# PSU_MAX1831_1V0_ALT.net
KiCad netlist of a schematic drawn in Altium Designer
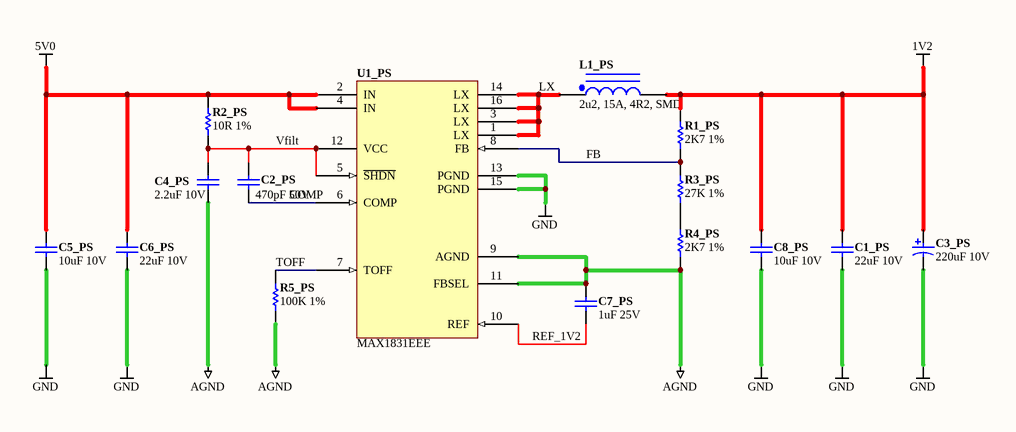
[diagram p0: PSU_MAX1831_1V0_ALT.SchDoc]

(export (version "E")
  (design (tool "Eeschema 10.0.6"))
  (components
    (comp (ref "C1_PS")
      (value "22uF 10V")
      (footprint "CAPC3225-STAR")
      (description "Capacitor, Ceramic, 22uF -20%/+80% 10V 1210 (3225) Y5V")
      (fields (field (name "TOLERANCE") "-20 / +80 %"))
      (libsource (lib "AltiumDesignLibrary") (part "CAP-NP"))
    )
    (comp (ref "C2_PS")
      (value "470pF 50V")
      (footprint "CAPC1005-STAR")
      (description "Capacitor, Ceramic, 470pF 5% 50V 0402 (1005) COG")
      (fields (field (name "TOLERANCE") "5 %"))
      (libsource (lib "AltiumDesignLibrary") (part "CAP-NP"))
    )
    (comp (ref "C3_PS")
      (value "220uF 10V")
      (footprint "CAPC7343-STAR")
      (description "Capacitor, Tantalum, 220uF 10% 10V MCCT-D (7343-31)")
      (fields (field (name "TOLERANCE") "10 %"))
      (libsource (lib "AltiumDesignLibrary") (part "CAP-P"))
    )
    (comp (ref "C4_PS")
      (value "2.2uF 10V")
      (footprint "CAPC1608-STAR")
      (description "Capacitor, Ceramic, 2.2uF 10% 10V 0603 (1608) X5R")
      (fields (field (name "TOLERANCE") "10 %"))
      (libsource (lib "AltiumDesignLibrary") (part "CAP-NP"))
    )
    (comp (ref "C5_PS")
      (value "10uF 10V")
      (footprint "CAPC2012-STAR")
      (description "Capacitor, Ceramic, 10uF 10% 10V 0805 (2012) X5R")
      (fields (field (name "TOLERANCE") "10 %"))
      (libsource (lib "AltiumDesignLibrary") (part "CAP-NP"))
    )
    (comp (ref "C6_PS")
      (value "22uF 10V")
      (footprint "CAPC3225-STAR")
      (description "Capacitor, Ceramic, 22uF -20%/+80% 10V 1210 (3225) Y5V")
      (fields (field (name "TOLERANCE") "-20 / +80 %"))
      (libsource (lib "AltiumDesignLibrary") (part "CAP-NP"))
    )
    (comp (ref "C7_PS")
      (value "1uF 25V")
      (footprint "CAPC3216-STAR")
      (description "Capacitor, Ceramic, 1uF 10% 25V 1206 (3216) X7R")
      (fields (field (name "TOLERANCE") "10 %"))
      (libsource (lib "AltiumDesignLibrary") (part "CAP-NP"))
    )
    (comp (ref "C8_PS")
      (value "10uF 10V")
      (footprint "CAPC2012-STAR")
      (description "Capacitor, Ceramic, 10uF 10% 10V 0805 (2012) X5R")
      (fields (field (name "TOLERANCE") "10 %"))
      (libsource (lib "AltiumDesignLibrary") (part "CAP-NP"))
    )
    (comp (ref "L1_PS")
      (value "2u2, 15A, 4R2, SMD")
      (footprint "IND-EPCOS-SMD-B82559")
      (description "Inductor, 2.2uH, 15A, 4R2, SMD")
      (libsource (lib "AltiumDesignLibrary") (part "IND-IRON-DOT"))
    )
    (comp (ref "R1_PS")
      (value "2K7 1%")
      (footprint "RESC1005-STAR")
      (description "Resistor, 2K7 1% 0402 (1005)")
      (fields (field (name "TOLERANCE") "1 %"))
      (libsource (lib "AltiumDesignLibrary") (part "RES"))
    )
    (comp (ref "R2_PS")
      (value "10R 1%")
      (footprint "RESC1005-STAR")
      (description "Resistor, 10R 1% 0402 (1005)")
      (fields (field (name "TOLERANCE") "1 %"))
      (libsource (lib "AltiumDesignLibrary") (part "RES"))
    )
    (comp (ref "R3_PS")
      (value "27K 1%")
      (footprint "RESC1005-STAR")
      (description "Resistor, 27K 1% 0402 (1005)")
      (fields (field (name "TOLERANCE") "1 %"))
      (libsource (lib "AltiumDesignLibrary") (part "RES"))
    )
    (comp (ref "R4_PS")
      (value "2K7 1%")
      (footprint "RESC1005-STAR")
      (description "Resistor, 2K7 1% 0402 (1005)")
      (fields (field (name "TOLERANCE") "1 %"))
      (libsource (lib "AltiumDesignLibrary") (part "RES"))
    )
    (comp (ref "R5_PS")
      (value "100K 1%")
      (footprint "RESC1005-STAR")
      (description "Resistor, 100K 1% 0402 (1005)")
      (fields (field (name "TOLERANCE") "1 %"))
      (libsource (lib "AltiumDesignLibrary") (part "RES"))
    )
    (comp (ref "U1_PS")
      (value "MAX1831EEE")
      (footprint "SOP63P602-16")
      (libsource (lib "AltiumDesignLibrary") (part "MAX1831-ALT"))
    )
  )
  (nets
    (net (code "1") (name "/COMP") (class "Default")
      (node (ref "C2_PS") (pin "2") (pinfunction "2_2") (pintype "passive"))
      (node (ref "U1_PS") (pin "6") (pinfunction "COMP_6") (pintype "input"))
    )
    (net (code "2") (name "/FB") (class "Default")
      (node (ref "R1_PS") (pin "2") (pinfunction "2_2") (pintype "passive"))
      (node (ref "R3_PS") (pin "1") (pinfunction "1_1") (pintype "passive"))
      (node (ref "U1_PS") (pin "8") (pinfunction "FB_8") (pintype "input"))
    )
    (net (code "3") (name "/LX") (class "Default")
      (node (ref "L1_PS") (pin "1") (pinfunction "1_1") (pintype "passive"))
      (node (ref "U1_PS") (pin "1") (pinfunction "LX_1") (pintype "power_in"))
      (node (ref "U1_PS") (pin "14") (pinfunction "LX_14") (pintype "power_in"))
      (node (ref "U1_PS") (pin "16") (pinfunction "LX_16") (pintype "power_in"))
      (node (ref "U1_PS") (pin "3") (pinfunction "LX_3") (pintype "power_in"))
    )
    (net (code "4") (name "/REF_1V2") (class "Default")
      (node (ref "C7_PS") (pin "2") (pinfunction "2_2") (pintype "passive"))
      (node (ref "U1_PS") (pin "10") (pinfunction "REF_10") (pintype "input"))
    )
    (net (code "5") (name "/TOFF") (class "Default")
      (node (ref "R5_PS") (pin "1") (pinfunction "1_1") (pintype "passive"))
      (node (ref "U1_PS") (pin "7") (pinfunction "TOFF_7") (pintype "input"))
    )
    (net (code "6") (name "/Vfilt") (class "Default")
      (node (ref "C2_PS") (pin "1") (pinfunction "1_1") (pintype "passive"))
      (node (ref "C4_PS") (pin "1") (pinfunction "1_1") (pintype "passive"))
      (node (ref "R2_PS") (pin "2") (pinfunction "2_2") (pintype "passive"))
      (node (ref "U1_PS") (pin "12") (pinfunction "VCC_12") (pintype "power_in"))
      (node (ref "U1_PS") (pin "5") (pinfunction "~{SHDN}_5") (pintype "input"))
    )
    (net (code "7") (name "1V2") (class "Default")
      (node (ref "C1_PS") (pin "1") (pinfunction "1_1") (pintype "passive"))
      (node (ref "C3_PS") (pin "1") (pinfunction "1_1") (pintype "passive"))
      (node (ref "C8_PS") (pin "1") (pinfunction "1_1") (pintype "passive"))
      (node (ref "L1_PS") (pin "2") (pinfunction "2_2") (pintype "passive"))
      (node (ref "R1_PS") (pin "1") (pinfunction "1_1") (pintype "passive"))
    )
    (net (code "8") (name "5V0") (class "Default")
      (node (ref "C5_PS") (pin "1") (pinfunction "1_1") (pintype "passive"))
      (node (ref "C6_PS") (pin "1") (pinfunction "1_1") (pintype "passive"))
      (node (ref "R2_PS") (pin "1") (pinfunction "1_1") (pintype "passive"))
      (node (ref "U1_PS") (pin "2") (pinfunction "IN_2") (pintype "power_in"))
      (node (ref "U1_PS") (pin "4") (pinfunction "IN_4") (pintype "power_in"))
    )
    (net (code "9") (name "AGND") (class "Default")
      (node (ref "C4_PS") (pin "2") (pinfunction "2_2") (pintype "passive"))
      (node (ref "C7_PS") (pin "1") (pinfunction "1_1") (pintype "passive"))
      (node (ref "R4_PS") (pin "2") (pinfunction "2_2") (pintype "passive"))
      (node (ref "R5_PS") (pin "2") (pinfunction "2_2") (pintype "passive"))
      (node (ref "U1_PS") (pin "11") (pinfunction "FBSEL_11") (pintype "passive"))
      (node (ref "U1_PS") (pin "9") (pinfunction "AGND_9") (pintype "power_in"))
    )
    (net (code "10") (name "GND") (class "Default")
      (node (ref "C1_PS") (pin "2") (pinfunction "2_2") (pintype "passive"))
      (node (ref "C3_PS") (pin "2") (pinfunction "2_2") (pintype "passive"))
      (node (ref "C5_PS") (pin "2") (pinfunction "2_2") (pintype "passive"))
      (node (ref "C6_PS") (pin "2") (pinfunction "2_2") (pintype "passive"))
      (node (ref "C8_PS") (pin "2") (pinfunction "2_2") (pintype "passive"))
      (node (ref "U1_PS") (pin "13") (pinfunction "PGND_13") (pintype "power_in"))
      (node (ref "U1_PS") (pin "15") (pinfunction "PGND_15") (pintype "power_in"))
    )
    (net (code "11") (name "Net-(R3_PS-Pad2)") (class "Default")
      (node (ref "R3_PS") (pin "2") (pinfunction "2_2") (pintype "passive"))
      (node (ref "R4_PS") (pin "1") (pinfunction "1_1") (pintype "passive"))
    )
  )
)
